# OctoSlime_TouchPad.net
KiCad netlist of a schematic drawn in EasyEDA Pro
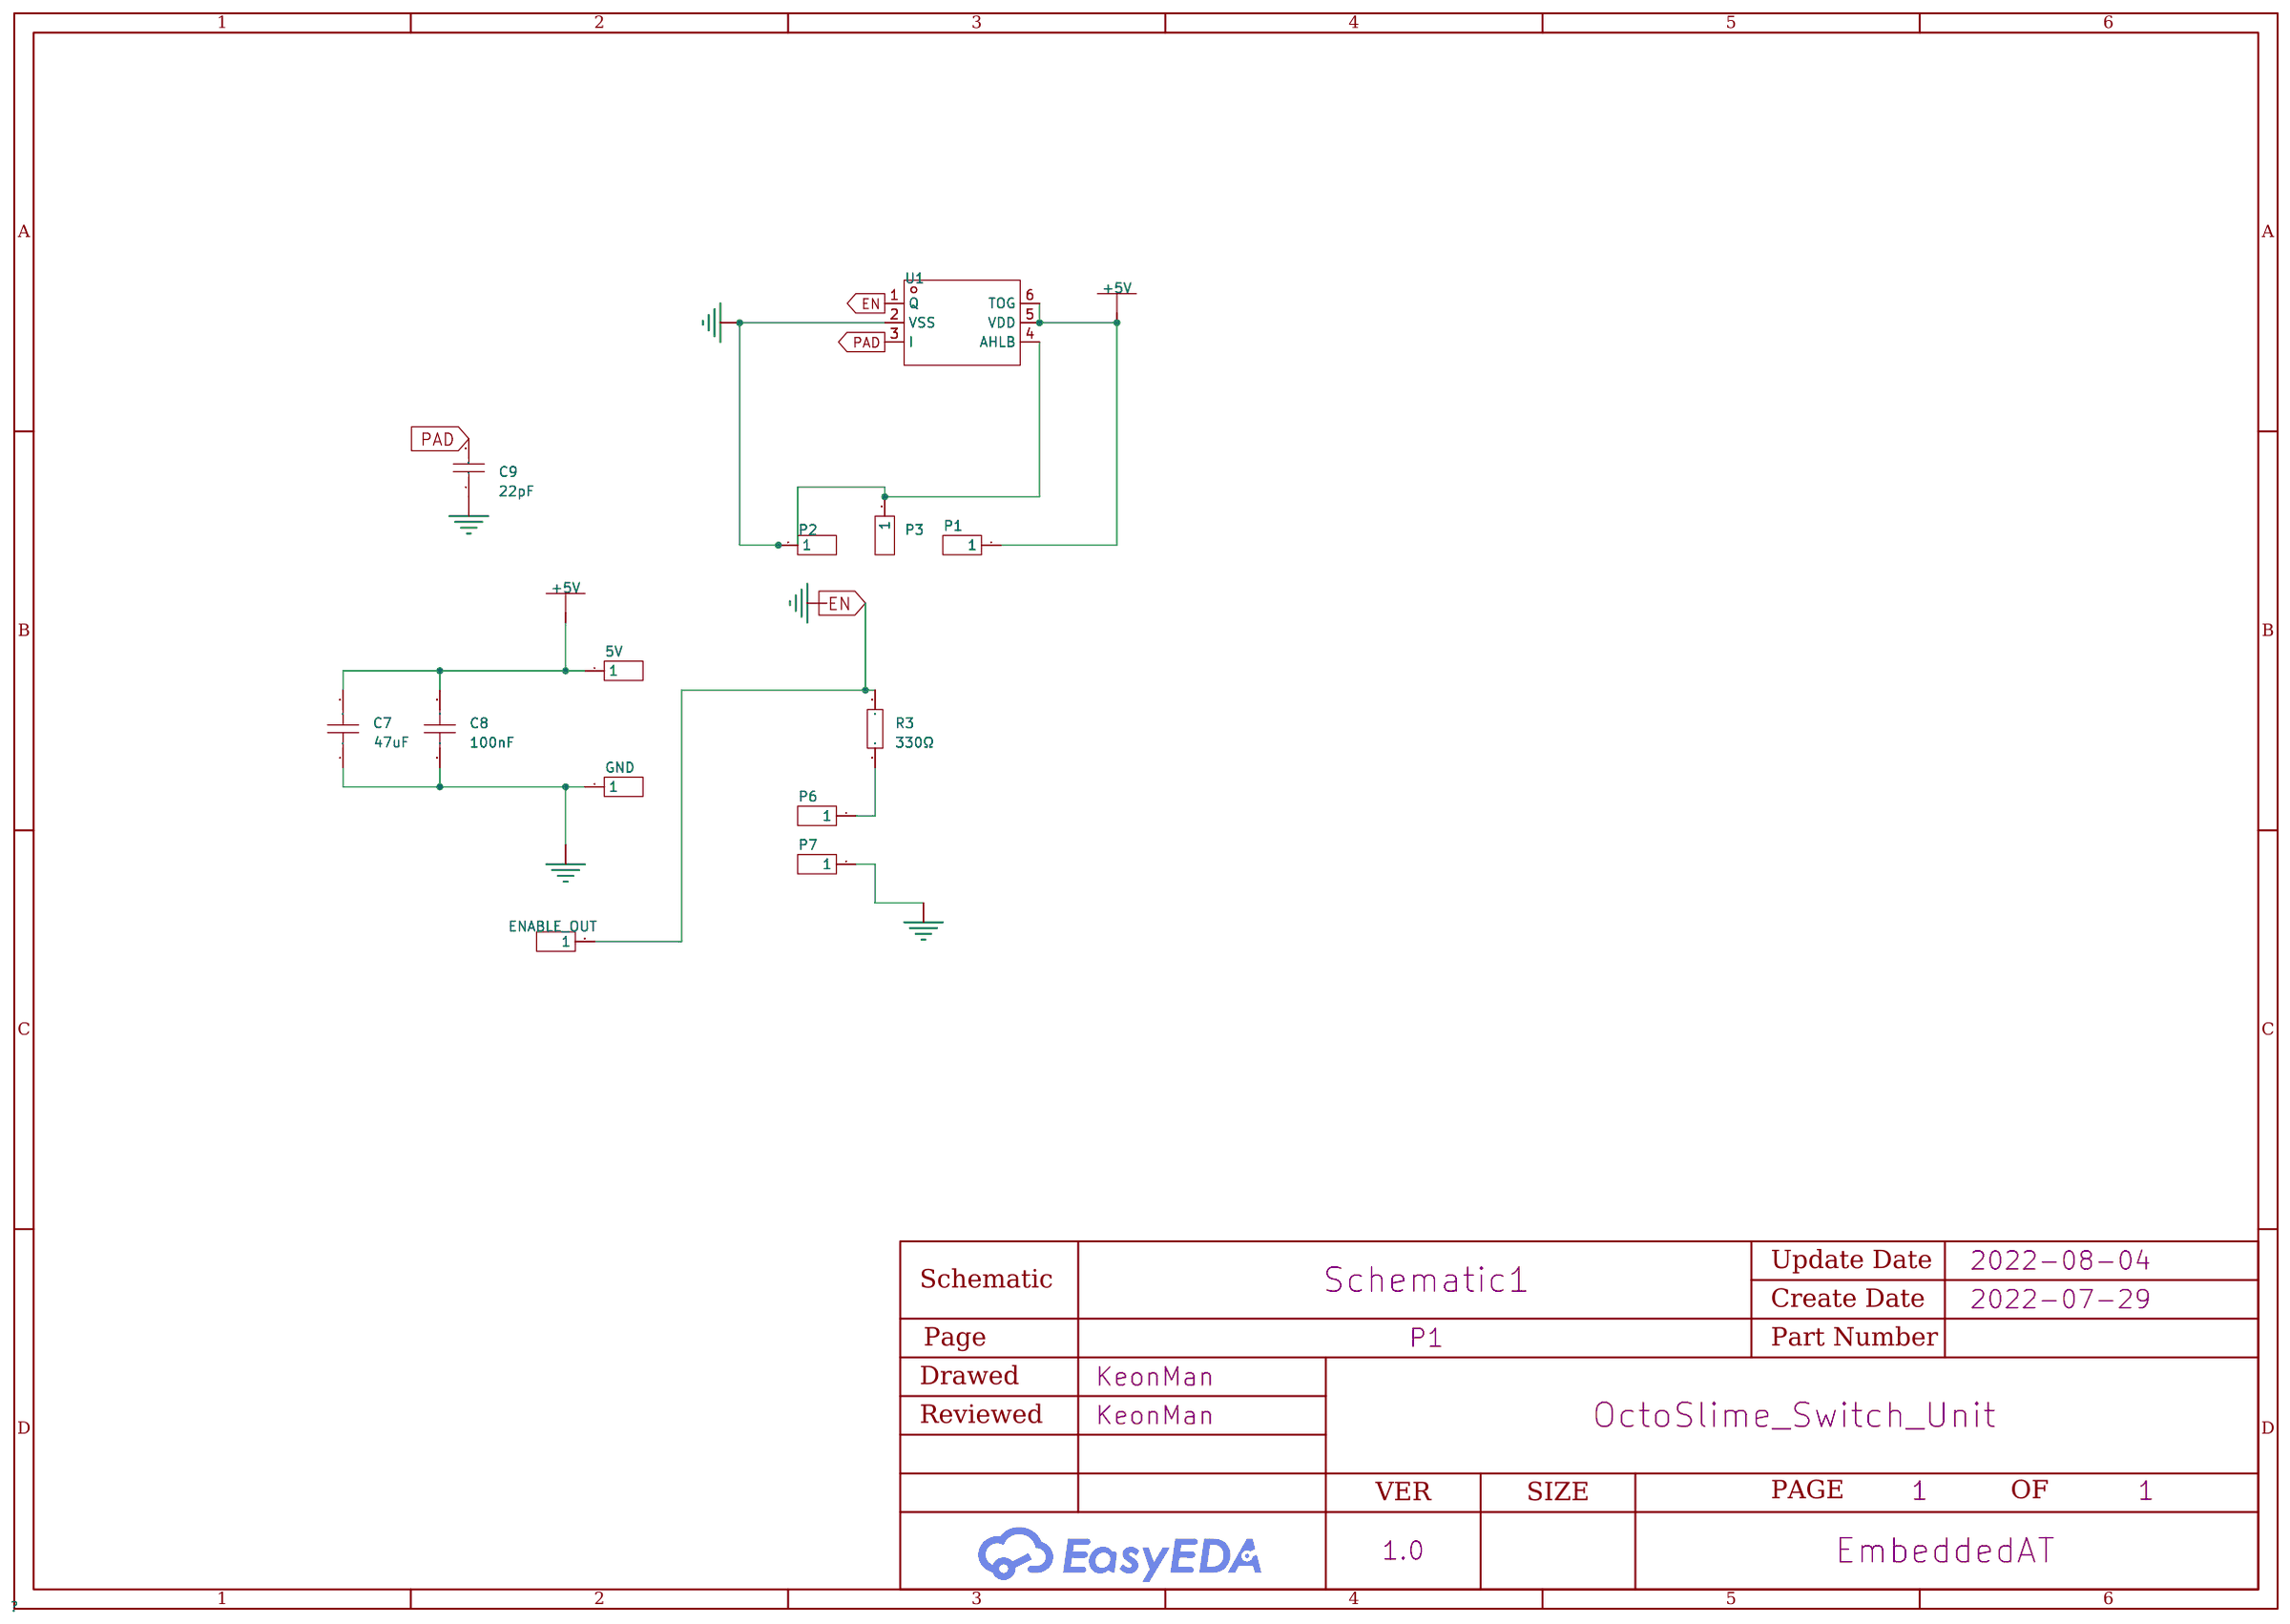
[diagram p0: schematic sheet]

(export (version "E")
  (design (tool "Eeschema 10.0.6"))
  (components
    (comp (ref "5V")
      (value "~")
      (footprint "easyedapro:HDR-TH_1P-P2.54-V-M")
      (description "间距:-;总PIN位数:1;排数:1;插针结构:-;行距:-;安装类型:直插;圆针/方针:-;额定电流:-;额定电压:-;配合针长度:-;塑高:-;触头材质:-;触头镀层:-;颜色:黑色;")
      (fields (field (name "Manufacturer Part") "2.54-1*1P针") (field (name "Manufacturer") "BOOMELE(博穆精密)"))
      (libsource (lib "easyedapro") (part "Header-Male-2.54_1x1"))
    )
    (comp (ref "C7")
      (value "47uF")
      (footprint "easyedapro:C1206")
      (description "容值:47uF;精度:±20%;额定电压:10V;温度系数:X5R;")
      (fields
        (field (name "Manufacturer Part") "CL31A476MPHNNNE")
        (field (name "Manufacturer") "SAMSUNG(三星)")
      )
      (libsource (lib "easyedapro") (part "CL31A476MPHNNNE"))
    )
    (comp (ref "C8")
      (value "100nF")
      (footprint "easyedapro:C0402")
      (description "容值:100nF;精度:±10%;额定电压:50V;温度系数:X7R;")
      (fields
        (field (name "Manufacturer Part") "CL05B104KB54PNC")
        (field (name "Manufacturer") "SAMSUNG(三星)")
      )
      (libsource (lib "easyedapro") (part "CL05B104KB54PNC"))
    )
    (comp (ref "C9")
      (value "22pF")
      (footprint "easyedapro:C0805")
      (description "容值:22pF;精度:±5%;额定电压:50V;温度系数:C0G;")
      (fields
        (field (name "Manufacturer Part") "CL21C220JBANNNC")
        (field (name "Manufacturer") "SAMSUNG(三星)")
      )
      (libsource (lib "easyedapro") (part "CL21C220JBANNNC"))
    )
    (comp (ref "ENABLE_OUT")
      (value "~")
      (footprint "easyedapro:HDR-TH_1P-P2.54-V-M")
      (description "间距:-;总PIN位数:1;排数:1;插针结构:-;行距:-;安装类型:直插;圆针/方针:-;额定电流:-;额定电压:-;配合针长度:-;塑高:-;触头材质:-;触头镀层:-;颜色:黑色;")
      (fields (field (name "Manufacturer Part") "2.54-1*1P针") (field (name "Manufacturer") "BOOMELE(博穆精密)"))
      (libsource (lib "easyedapro") (part "Header-Male-2.54_1x1"))
    )
    (comp (ref "GND")
      (value "~")
      (footprint "easyedapro:HDR-TH_1P-P2.54-V-M")
      (description "间距:-;总PIN位数:1;排数:1;插针结构:-;行距:-;安装类型:直插;圆针/方针:-;额定电流:-;额定电压:-;配合针长度:-;塑高:-;触头材质:-;触头镀层:-;颜色:黑色;")
      (fields (field (name "Manufacturer Part") "2.54-1*1P针") (field (name "Manufacturer") "BOOMELE(博穆精密)"))
      (libsource (lib "easyedapro") (part "Header-Male-2.54_1x1"))
    )
    (comp (ref "P1")
      (value "~")
      (footprint "easyedapro:HDR-TH_1P-P2.54-V-M")
      (description "间距:-;总PIN位数:1;排数:1;插针结构:-;行距:-;安装类型:直插;圆针/方针:-;额定电流:-;额定电压:-;配合针长度:-;塑高:-;触头材质:-;触头镀层:-;颜色:黑色;")
      (fields (field (name "Manufacturer Part") "2.54-1*1P针") (field (name "Manufacturer") "BOOMELE(博穆精密)"))
      (libsource (lib "easyedapro") (part "Header-Male-2.54_1x1"))
    )
    (comp (ref "P2")
      (value "~")
      (footprint "easyedapro:HDR-TH_1P-P2.54-V-M")
      (description "间距:-;总PIN位数:1;排数:1;插针结构:-;行距:-;安装类型:直插;圆针/方针:-;额定电流:-;额定电压:-;配合针长度:-;塑高:-;触头材质:-;触头镀层:-;颜色:黑色;")
      (fields (field (name "Manufacturer Part") "2.54-1*1P针") (field (name "Manufacturer") "BOOMELE(博穆精密)"))
      (libsource (lib "easyedapro") (part "Header-Male-2.54_1x1"))
    )
    (comp (ref "P3")
      (value "~")
      (footprint "easyedapro:HDR-TH_1P-P2.54-V-M")
      (description "间距:-;总PIN位数:1;排数:1;插针结构:-;行距:-;安装类型:直插;圆针/方针:-;额定电流:-;额定电压:-;配合针长度:-;塑高:-;触头材质:-;触头镀层:-;颜色:黑色;")
      (fields (field (name "Manufacturer Part") "2.54-1*1P针") (field (name "Manufacturer") "BOOMELE(博穆精密)"))
      (libsource (lib "easyedapro") (part "Header-Male-2.54_1x1"))
    )
    (comp (ref "P6")
      (value "~")
      (footprint "easyedapro:HDR-TH_1P-P2.54-V-M")
      (description "间距:-;总PIN位数:1;排数:1;插针结构:-;行距:-;安装类型:直插;圆针/方针:-;额定电流:-;额定电压:-;配合针长度:-;塑高:-;触头材质:-;触头镀层:-;颜色:黑色;")
      (fields (field (name "Manufacturer Part") "2.54-1*1P针") (field (name "Manufacturer") "BOOMELE(博穆精密)"))
      (libsource (lib "easyedapro") (part "Header-Male-2.54_1x1"))
    )
    (comp (ref "P7")
      (value "~")
      (footprint "easyedapro:HDR-TH_1P-P2.54-V-M")
      (description "间距:-;总PIN位数:1;排数:1;插针结构:-;行距:-;安装类型:直插;圆针/方针:-;额定电流:-;额定电压:-;配合针长度:-;塑高:-;触头材质:-;触头镀层:-;颜色:黑色;")
      (fields (field (name "Manufacturer Part") "2.54-1*1P针") (field (name "Manufacturer") "BOOMELE(博穆精密)"))
      (libsource (lib "easyedapro") (part "Header-Male-2.54_1x1"))
    )
    (comp (ref "R3")
      (value "330Ω")
      (footprint "easyedapro:R0805")
      (description "电阻类型:厚膜电阻;阻值:330Ω;精度:±1%;功率:125mW;温度系数:±100ppm/;最大工作电压:150V;工作温度范围:-55~+155;")
      (fields
        (field (name "Manufacturer Part") "0805W8F3300T5E")
        (field (name "Manufacturer") "UNI-ROYAL(厚声)")
      )
      (libsource (lib "easyedapro") (part "0805W8F3300T5E"))
    )
    (comp (ref "U1")
      (value "~")
      (footprint "easyedapro:SOT-23-6_L2.9-W1.6-P0.95-LS2.8-BR")
      (description "单按键触摸感应开关")
      (fields (field (name "Manufacturer Part") "TTP223E-BA6") (field (name "Manufacturer") "TONTEK(台湾通泰)"))
      (libsource (lib "easyedapro") (part "TTP223E-BA6"))
    )
  )
  (nets
    (net (code "1") (name "+5V") (class "Default")
      (node (ref "5V") (pin "1") (pinfunction "1_1") (pintype "input"))
      (node (ref "C7") (pin "2") (pinfunction "2_2") (pintype "input"))
      (node (ref "C8") (pin "2") (pinfunction "2_2") (pintype "input"))
      (node (ref "P1") (pin "1") (pinfunction "1_1") (pintype "input"))
      (node (ref "U1") (pin "5") (pinfunction "VDD_5") (pintype "input"))
      (node (ref "U1") (pin "6") (pinfunction "TOG_6") (pintype "input"))
    )
    (net (code "2") (name "EN") (class "Default")
      (node (ref "ENABLE_OUT") (pin "1") (pinfunction "1_1") (pintype "input"))
      (node (ref "R3") (pin "2") (pinfunction "2_2") (pintype "input"))
      (node (ref "U1") (pin "1") (pinfunction "Q_1") (pintype "input"))
    )
    (net (code "3") (name "GND") (class "Default")
      (node (ref "C7") (pin "1") (pinfunction "1_1") (pintype "input"))
      (node (ref "C8") (pin "1") (pinfunction "1_1") (pintype "input"))
      (node (ref "C9") (pin "1") (pinfunction "1_1") (pintype "input"))
      (node (ref "GND") (pin "1") (pinfunction "1_1") (pintype "input"))
      (node (ref "P2") (pin "1") (pinfunction "1_1") (pintype "input"))
      (node (ref "P3") (pin "1") (pinfunction "1_1") (pintype "input"))
      (node (ref "P7") (pin "1") (pinfunction "1_1") (pintype "input"))
      (node (ref "U1") (pin "2") (pinfunction "VSS_2") (pintype "input"))
      (node (ref "U1") (pin "4") (pinfunction "AHLB_4") (pintype "input"))
    )
    (net (code "4") (name "Net-(P6-Pad1)") (class "Default")
      (node (ref "P6") (pin "1") (pinfunction "1_1") (pintype "input"))
      (node (ref "R3") (pin "1") (pinfunction "1_1") (pintype "input"))
    )
    (net (code "5") (name "PAD") (class "Default")
      (node (ref "C9") (pin "2") (pinfunction "2_2") (pintype "input"))
      (node (ref "U1") (pin "3") (pinfunction "I_3") (pintype "input"))
    )
  )
)
